# Top.net
KiCad netlist of a schematic drawn in Altium Designer
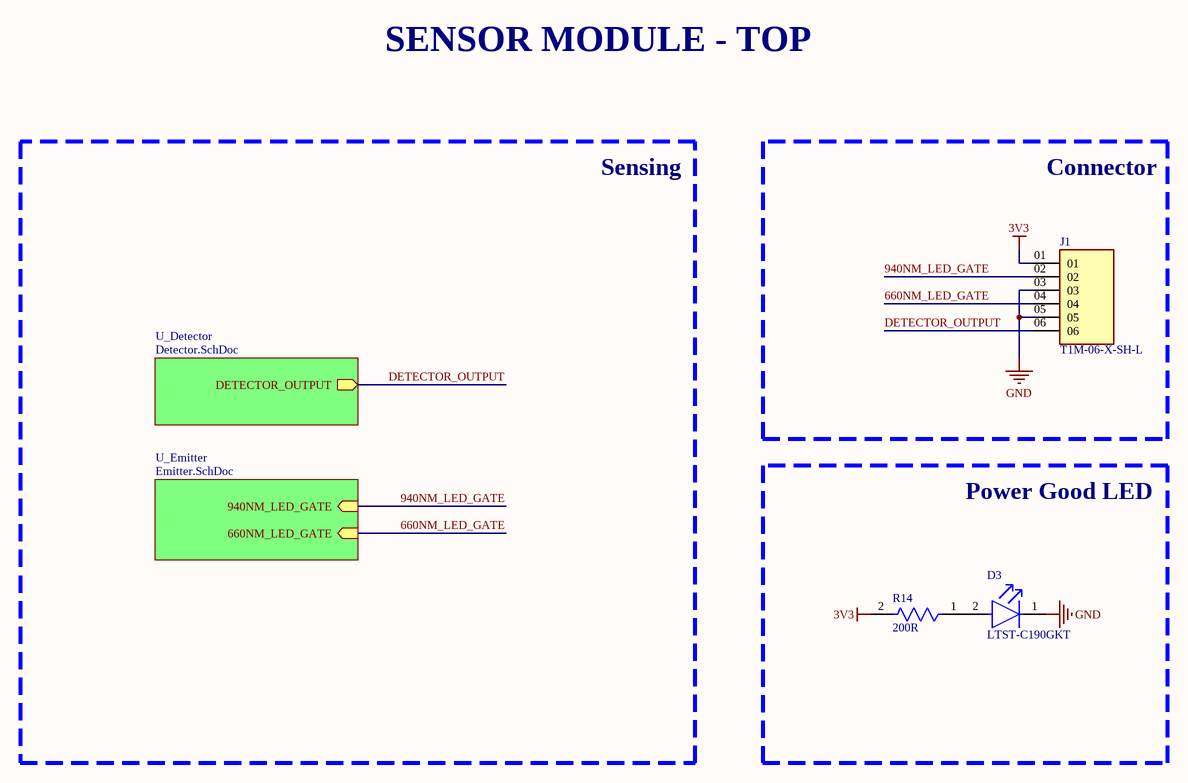
[diagram p0: Top.SchDoc]

(export (version "E")
  (design (tool "Eeschema 10.0.6"))
  (components
    (comp (ref "D3")
      (value "LTST-C190GKT")
      (footprint "FP-LTST-C190GKT-MFG")
      (description "LED GREEN CLEAR CHIP SMD")
      (fields (field (name "VOLTAGE") "2V"))
      (libsource (lib "Altium Content Vault") (part "8706943c75ba83719d021d2fdc84c58"))
    )
    (comp (ref "J1")
      (value "T1M-06-X-SH-L")
      (footprint "SAMTEC_T1M-06-X-SH-L")
      (description "Connector Header Surface Mount, Right Angle 6 position 0.039\" (1.00mm)")
      (fields (field (name "MF") "Samtec"))
      (libsource (lib "Schlib1") (part "T1M-06-X-SH-L"))
    )
    (comp (ref "R14")
      (value "CRCW0603200RFKEA")
      (footprint "FP-CRCW0603-e3-MFG")
      (description "RES Thick Film, 200Ω, 1%, 0.1W, 100ppm/°C, 0603")
      (fields (field (name "TOLERANCE") "1%") (field (name "RESISTANCE") "200R"))
      (libsource (lib "Altium Content Vault") (part "1029c3af85768c4190bb7ad29bc67b5"))
    )
  )
  (nets
    (net (code "1") (name "/660NM_LED_GATE") (class "Default")
      (node (ref "J1") (pin "04") (pinfunction "04_04") (pintype "passive"))
    )
    (net (code "2") (name "/940NM_LED_GATE") (class "Default")
      (node (ref "J1") (pin "02") (pinfunction "02_02") (pintype "passive"))
    )
    (net (code "3") (name "/DETECTOR_OUTPUT") (class "Default")
      (node (ref "J1") (pin "06") (pinfunction "06_06") (pintype "passive"))
    )
    (net (code "4") (name "3V3") (class "Default")
      (node (ref "J1") (pin "01") (pinfunction "01_01") (pintype "passive"))
      (node (ref "R14") (pin "2") (pinfunction "2_2") (pintype "passive"))
    )
    (net (code "5") (name "GND") (class "Default")
      (node (ref "D3") (pin "1") (pinfunction "C_1") (pintype "passive"))
      (node (ref "J1") (pin "03") (pinfunction "03_03") (pintype "passive"))
      (node (ref "J1") (pin "05") (pinfunction "05_05") (pintype "passive"))
    )
    (net (code "6") (name "Net-(D3-A)") (class "Default")
      (node (ref "D3") (pin "2") (pinfunction "A_2") (pintype "passive"))
      (node (ref "R14") (pin "1") (pinfunction "1_1") (pintype "passive"))
    )
  )
)
